# Break_out.net
KiCad netlist of a schematic drawn in EAGLE
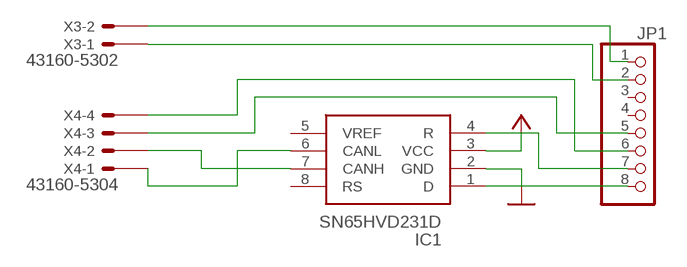
[diagram p0: schematic, sheet 1]

(export (version "E")
  (design (tool "Eeschema 10.0.6"))
  (components
    (comp (ref "IC1")
      (value "SN65HVD231D")
      (footprint "eagle-import:SOIC127P600X175-8N")
      (fields (field (name "MOUSER_PART_NUMBER") "595-SN65HVD231D"))
      (libsource (lib "eagle-import") (part "SN65HVD231D"))
    )
    (comp (ref "JP1")
      (value "PINHD-1X8BIG")
      (footprint "eagle-import:1X08-BIG")
      (libsource (lib "eagle-import") (part "PINHD-1X8BIG"))
    )
    (comp (ref "X3")
      (value "43160-5302")
      (footprint "eagle-import:43160-XX02")
      (fields (field (name "MF") "MOLEX"))
      (libsource (lib "eagle-import") (part "43160-0253"))
    )
    (comp (ref "X4")
      (value "43160-5304")
      (footprint "eagle-import:43160-XX04")
      (fields (field (name "MF") "MOLEX"))
      (libsource (lib "eagle-import") (part "43160-0453"))
    )
  )
  (nets
    (net (code "1") (name "GND") (class "Default")
      (node (ref "IC1") (pin "2") (pinfunction "GND_2") (pintype "bidirectional"))
    )
    (net (code "2") (name "Net-(IC1-CANH)") (class "Default")
      (node (ref "IC1") (pin "7") (pinfunction "CANH_7") (pintype "bidirectional"))
      (node (ref "X4") (pin "2@1") (pinfunction "S_2@1") (pintype "passive"))
    )
    (net (code "3") (name "Net-(IC1-CANL)") (class "Default")
      (node (ref "IC1") (pin "6") (pinfunction "CANL_6") (pintype "bidirectional"))
      (node (ref "X4") (pin "1@1") (pinfunction "S_1@1") (pintype "passive"))
    )
    (net (code "4") (name "Net-(IC1-D)") (class "Default")
      (node (ref "IC1") (pin "1") (pinfunction "D_1") (pintype "bidirectional"))
      (node (ref "JP1") (pin "8") (pinfunction "8_8") (pintype "passive"))
    )
    (net (code "5") (name "Net-(IC1-R)") (class "Default")
      (node (ref "IC1") (pin "4") (pinfunction "R_4") (pintype "bidirectional"))
      (node (ref "JP1") (pin "7") (pinfunction "7_7") (pintype "passive"))
    )
    (net (code "6") (name "Net-(JP1-Pad1)") (class "Default")
      (node (ref "JP1") (pin "1") (pinfunction "1_1") (pintype "passive"))
      (node (ref "X3") (pin "2@1") (pinfunction "S_2@1") (pintype "passive"))
    )
    (net (code "7") (name "Net-(JP1-Pad2)") (class "Default")
      (node (ref "JP1") (pin "2") (pinfunction "2_2") (pintype "passive"))
      (node (ref "X3") (pin "1@1") (pinfunction "S_1@1") (pintype "passive"))
    )
    (net (code "8") (name "Net-(JP1-Pad5)") (class "Default")
      (node (ref "JP1") (pin "5") (pinfunction "5_5") (pintype "passive"))
      (node (ref "X4") (pin "3@1") (pinfunction "S_3@1") (pintype "passive"))
    )
    (net (code "9") (name "Net-(JP1-Pad6)") (class "Default")
      (node (ref "JP1") (pin "6") (pinfunction "6_6") (pintype "passive"))
      (node (ref "X4") (pin "4@1") (pinfunction "S_4@1") (pintype "passive"))
    )
    (net (code "10") (name "VCC") (class "Default")
      (node (ref "IC1") (pin "3") (pinfunction "VCC_3") (pintype "bidirectional"))
    )
    (net (code "11") (name "unconnected-(IC1-RS-Pad8)") (class "Default")
      (node (ref "IC1") (pin "8") (pinfunction "RS_8") (pintype "bidirectional"))
    )
    (net (code "12") (name "unconnected-(IC1-VREF-Pad5)") (class "Default")
      (node (ref "IC1") (pin "5") (pinfunction "VREF_5") (pintype "bidirectional"))
    )
    (net (code "13") (name "unconnected-(JP1-Pad3)") (class "Default")
      (node (ref "JP1") (pin "3") (pinfunction "3_3") (pintype "passive"))
    )
    (net (code "14") (name "unconnected-(JP1-Pad4)") (class "Default")
      (node (ref "JP1") (pin "4") (pinfunction "4_4") (pintype "passive"))
    )
    (net (code "15") (name "unconnected-(X3A-S-Pad1@2)") (class "Default")
      (node (ref "X3") (pin "1@2") (pinfunction "S_1@2") (pintype "passive"))
    )
    (net (code "16") (name "unconnected-(X3B-S-Pad2@2)") (class "Default")
      (node (ref "X3") (pin "2@2") (pinfunction "S_2@2") (pintype "passive"))
    )
    (net (code "17") (name "unconnected-(X4A-S-Pad1@2)") (class "Default")
      (node (ref "X4") (pin "1@2") (pinfunction "S_1@2") (pintype "passive"))
    )
    (net (code "18") (name "unconnected-(X4B-S-Pad2@2)") (class "Default")
      (node (ref "X4") (pin "2@2") (pinfunction "S_2@2") (pintype "passive"))
    )
    (net (code "19") (name "unconnected-(X4C-S-Pad3@2)") (class "Default")
      (node (ref "X4") (pin "3@2") (pinfunction "S_3@2") (pintype "passive"))
    )
    (net (code "20") (name "unconnected-(X4D-S-Pad4@2)") (class "Default")
      (node (ref "X4") (pin "4@2") (pinfunction "S_4@2") (pintype "passive"))
    )
  )
)
